# LCD2004_Adapter.net
KiCad netlist of a schematic drawn in EAGLE
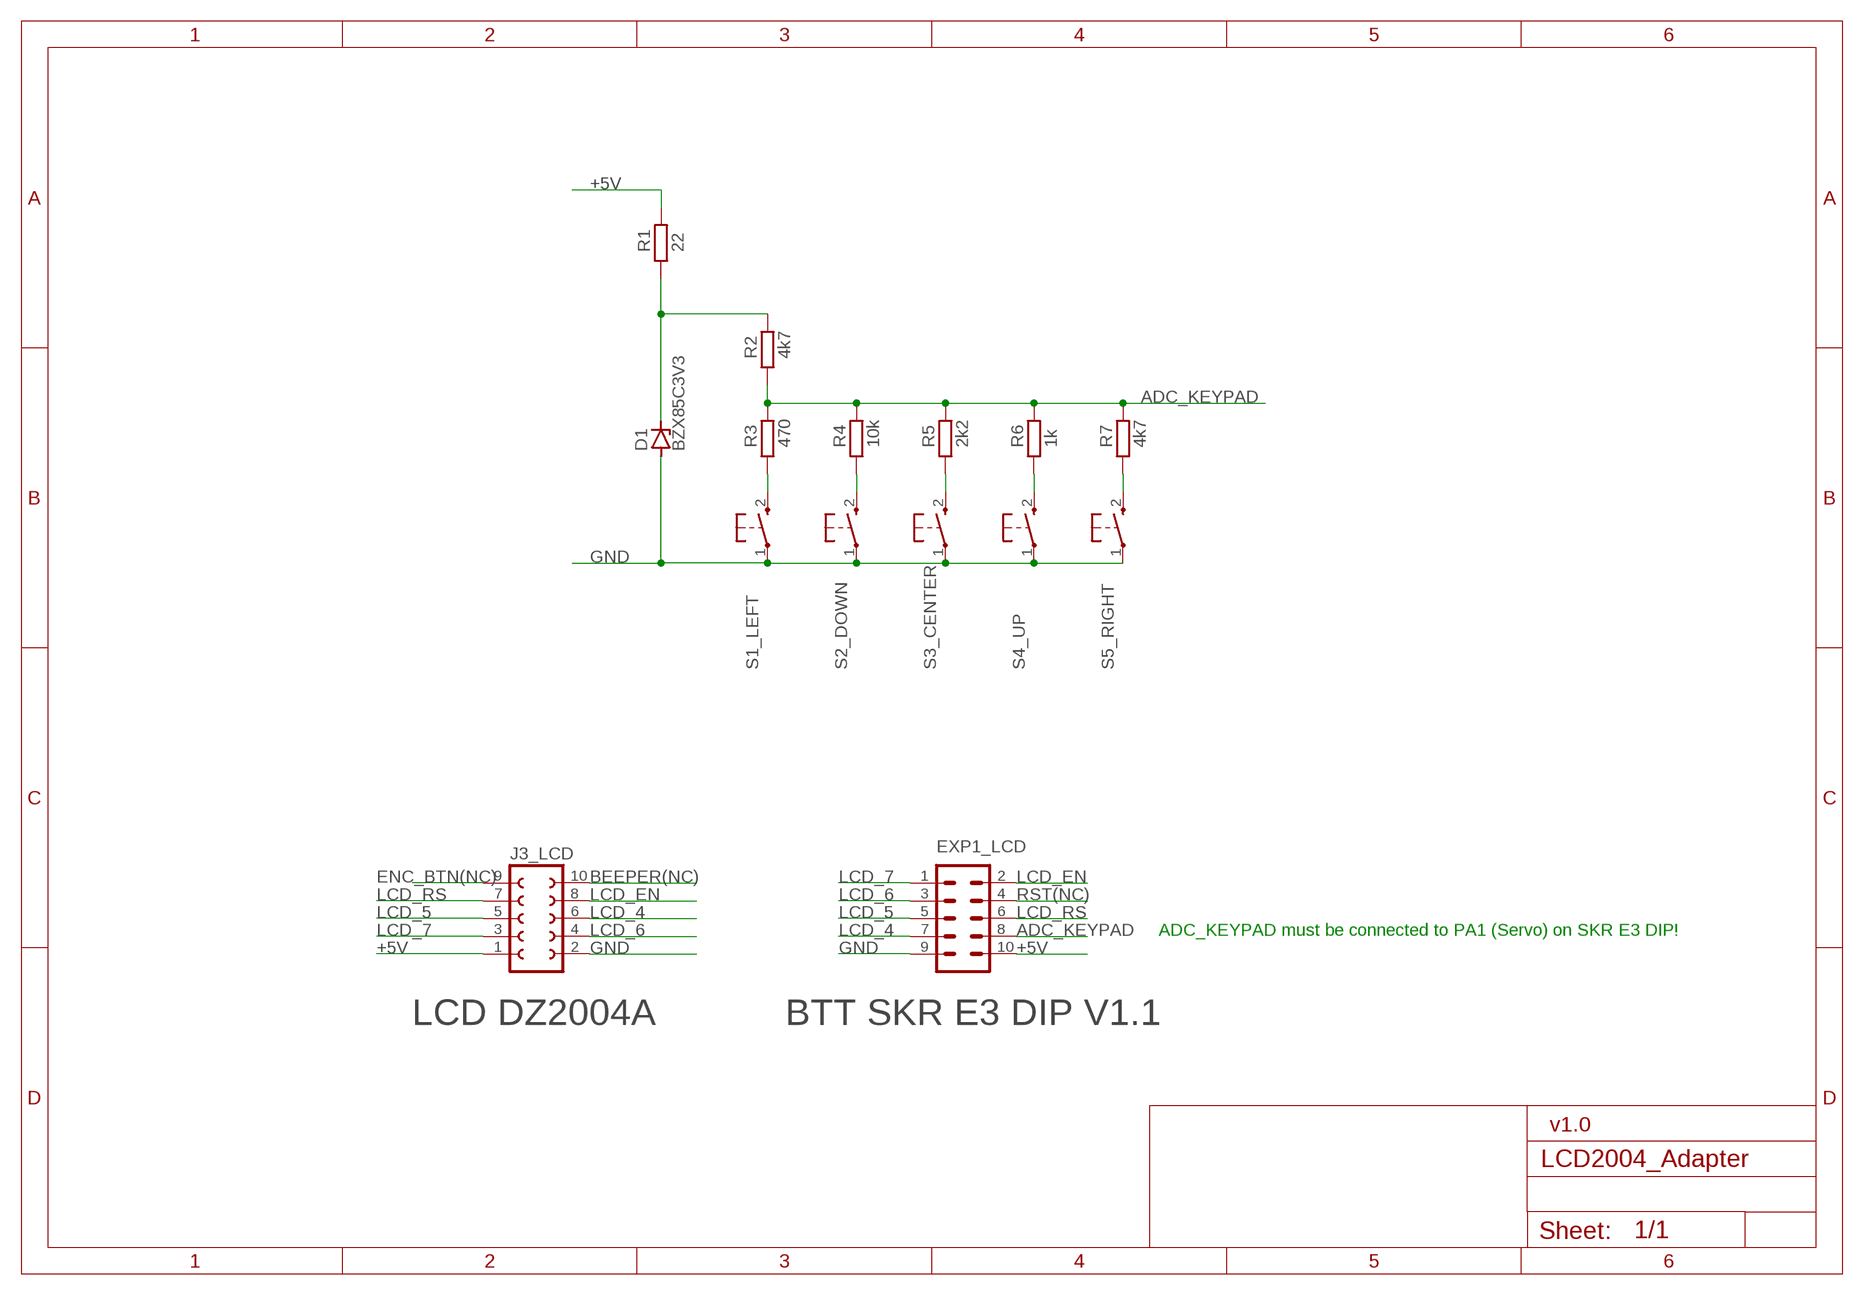
[diagram p0: schematic, sheet 1]

(export (version "E")
  (design (tool "Eeschema 10.0.6"))
  (components
    (comp (ref "D1")
      (value "BZX85C3V3")
      (footprint "eagle-import:DO41Z10")
      (libsource (lib "eagle-import") (part "BZX85"))
    )
    (comp (ref "EXP1_LCD")
      (value "ML10")
      (footprint "eagle-import:ML10")
      (libsource (lib "eagle-import") (part "ML10"))
    )
    (comp (ref "J3_LCD")
      (value "FE05-2")
      (footprint "eagle-import:FE05-2")
      (libsource (lib "eagle-import") (part "FE05-2"))
    )
    (comp (ref "R1")
      (value "22")
      (footprint "eagle-import:0207_10")
      (libsource (lib "eagle-import") (part "R-EU_0207/10"))
    )
    (comp (ref "R2")
      (value "4k7")
      (footprint "eagle-import:0207_10")
      (libsource (lib "eagle-import") (part "R-EU_0207/10"))
    )
    (comp (ref "R3")
      (value "470")
      (footprint "eagle-import:0207_10")
      (libsource (lib "eagle-import") (part "R-EU_0207/10"))
    )
    (comp (ref "R4")
      (value "10k")
      (footprint "eagle-import:0207_10")
      (libsource (lib "eagle-import") (part "R-EU_0207/10"))
    )
    (comp (ref "R5")
      (value "2k2")
      (footprint "eagle-import:0207_10")
      (libsource (lib "eagle-import") (part "R-EU_0207/10"))
    )
    (comp (ref "R6")
      (value "1k")
      (footprint "eagle-import:0207_10")
      (libsource (lib "eagle-import") (part "R-EU_0207/10"))
    )
    (comp (ref "R7")
      (value "4k7")
      (footprint "eagle-import:0207_10")
      (libsource (lib "eagle-import") (part "R-EU_0207/10"))
    )
    (comp (ref "S1_LEFT")
      (value "KURZHUBTASTER")
      (footprint "eagle-import:B3F-10XX")
      (libsource (lib "eagle-import") (part "KURZHUBTASTER"))
    )
    (comp (ref "S2_DOWN")
      (value "KURZHUBTASTER")
      (footprint "eagle-import:B3F-10XX")
      (libsource (lib "eagle-import") (part "KURZHUBTASTER"))
    )
    (comp (ref "S3_CENTER")
      (value "KURZHUBTASTER")
      (footprint "eagle-import:B3F-10XX")
      (libsource (lib "eagle-import") (part "KURZHUBTASTER"))
    )
    (comp (ref "S4_UP")
      (value "KURZHUBTASTER")
      (footprint "eagle-import:B3F-10XX")
      (libsource (lib "eagle-import") (part "KURZHUBTASTER"))
    )
    (comp (ref "S5_RIGHT")
      (value "KURZHUBTASTER")
      (footprint "eagle-import:B3F-10XX")
      (libsource (lib "eagle-import") (part "KURZHUBTASTER"))
    )
  )
  (nets
    (net (code "1") (name "/+5V") (class "Default")
      (node (ref "EXP1_LCD") (pin "10") (pinfunction "10_10") (pintype "passive"))
      (node (ref "J3_LCD") (pin "1") (pinfunction "1_1") (pintype "passive"))
      (node (ref "R1") (pin "2") (pinfunction "2_2") (pintype "passive"))
    )
    (net (code "2") (name "/ADC_KEYPAD") (class "Default")
      (node (ref "EXP1_LCD") (pin "8") (pinfunction "8_8") (pintype "passive"))
      (node (ref "R2") (pin "1") (pinfunction "1_1") (pintype "passive"))
      (node (ref "R3") (pin "2") (pinfunction "2_2") (pintype "passive"))
      (node (ref "R4") (pin "2") (pinfunction "2_2") (pintype "passive"))
      (node (ref "R5") (pin "2") (pinfunction "2_2") (pintype "passive"))
      (node (ref "R6") (pin "2") (pinfunction "2_2") (pintype "passive"))
      (node (ref "R7") (pin "2") (pinfunction "2_2") (pintype "passive"))
    )
    (net (code "3") (name "/BEEPER(NC)") (class "Default")
      (node (ref "J3_LCD") (pin "10") (pinfunction "10_10") (pintype "passive"))
    )
    (net (code "4") (name "/ENC_BTN(NC)") (class "Default")
      (node (ref "J3_LCD") (pin "9") (pinfunction "9_9") (pintype "passive"))
    )
    (net (code "5") (name "/GND") (class "Default")
      (node (ref "D1") (pin "A") (pinfunction "A_A") (pintype "passive"))
      (node (ref "EXP1_LCD") (pin "9") (pinfunction "9_9") (pintype "passive"))
      (node (ref "J3_LCD") (pin "2") (pinfunction "2_2") (pintype "passive"))
      (node (ref "S1_LEFT") (pin "1") (pinfunction "P_1") (pintype "passive"))
      (node (ref "S2_DOWN") (pin "1") (pinfunction "P_1") (pintype "passive"))
      (node (ref "S3_CENTER") (pin "1") (pinfunction "P_1") (pintype "passive"))
      (node (ref "S4_UP") (pin "1") (pinfunction "P_1") (pintype "passive"))
      (node (ref "S5_RIGHT") (pin "1") (pinfunction "P_1") (pintype "passive"))
    )
    (net (code "6") (name "/LCD_4") (class "Default")
      (node (ref "EXP1_LCD") (pin "7") (pinfunction "7_7") (pintype "passive"))
      (node (ref "J3_LCD") (pin "6") (pinfunction "6_6") (pintype "passive"))
    )
    (net (code "7") (name "/LCD_5") (class "Default")
      (node (ref "EXP1_LCD") (pin "5") (pinfunction "5_5") (pintype "passive"))
      (node (ref "J3_LCD") (pin "5") (pinfunction "5_5") (pintype "passive"))
    )
    (net (code "8") (name "/LCD_6") (class "Default")
      (node (ref "EXP1_LCD") (pin "3") (pinfunction "3_3") (pintype "passive"))
      (node (ref "J3_LCD") (pin "4") (pinfunction "4_4") (pintype "passive"))
    )
    (net (code "9") (name "/LCD_7") (class "Default")
      (node (ref "EXP1_LCD") (pin "1") (pinfunction "1_1") (pintype "passive"))
      (node (ref "J3_LCD") (pin "3") (pinfunction "3_3") (pintype "passive"))
    )
    (net (code "10") (name "/LCD_EN") (class "Default")
      (node (ref "EXP1_LCD") (pin "2") (pinfunction "2_2") (pintype "passive"))
      (node (ref "J3_LCD") (pin "8") (pinfunction "8_8") (pintype "passive"))
    )
    (net (code "11") (name "/LCD_RS") (class "Default")
      (node (ref "EXP1_LCD") (pin "6") (pinfunction "6_6") (pintype "passive"))
      (node (ref "J3_LCD") (pin "7") (pinfunction "7_7") (pintype "passive"))
    )
    (net (code "12") (name "/RST(NC)") (class "Default")
      (node (ref "EXP1_LCD") (pin "4") (pinfunction "4_4") (pintype "passive"))
    )
    (net (code "13") (name "Net-(D1-PadC)") (class "Default")
      (node (ref "D1") (pin "C") (pinfunction "C_C") (pintype "passive"))
      (node (ref "R1") (pin "1") (pinfunction "1_1") (pintype "passive"))
      (node (ref "R2") (pin "2") (pinfunction "2_2") (pintype "passive"))
    )
    (net (code "14") (name "Net-(S1_LEFT-S)") (class "Default")
      (node (ref "R3") (pin "1") (pinfunction "1_1") (pintype "passive"))
      (node (ref "S1_LEFT") (pin "2") (pinfunction "S_2") (pintype "passive"))
    )
    (net (code "15") (name "Net-(S2_DOWN-S)") (class "Default")
      (node (ref "R4") (pin "1") (pinfunction "1_1") (pintype "passive"))
      (node (ref "S2_DOWN") (pin "2") (pinfunction "S_2") (pintype "passive"))
    )
    (net (code "16") (name "Net-(S3_CENTER-S)") (class "Default")
      (node (ref "R5") (pin "1") (pinfunction "1_1") (pintype "passive"))
      (node (ref "S3_CENTER") (pin "2") (pinfunction "S_2") (pintype "passive"))
    )
    (net (code "17") (name "Net-(S4_UP-S)") (class "Default")
      (node (ref "R6") (pin "1") (pinfunction "1_1") (pintype "passive"))
      (node (ref "S4_UP") (pin "2") (pinfunction "S_2") (pintype "passive"))
    )
    (net (code "18") (name "Net-(S5_RIGHT-S)") (class "Default")
      (node (ref "R7") (pin "1") (pinfunction "1_1") (pintype "passive"))
      (node (ref "S5_RIGHT") (pin "2") (pinfunction "S_2") (pintype "passive"))
    )
  )
)
